# Soprano2G-024.net
KiCad netlist of a schematic drawn in EAGLE
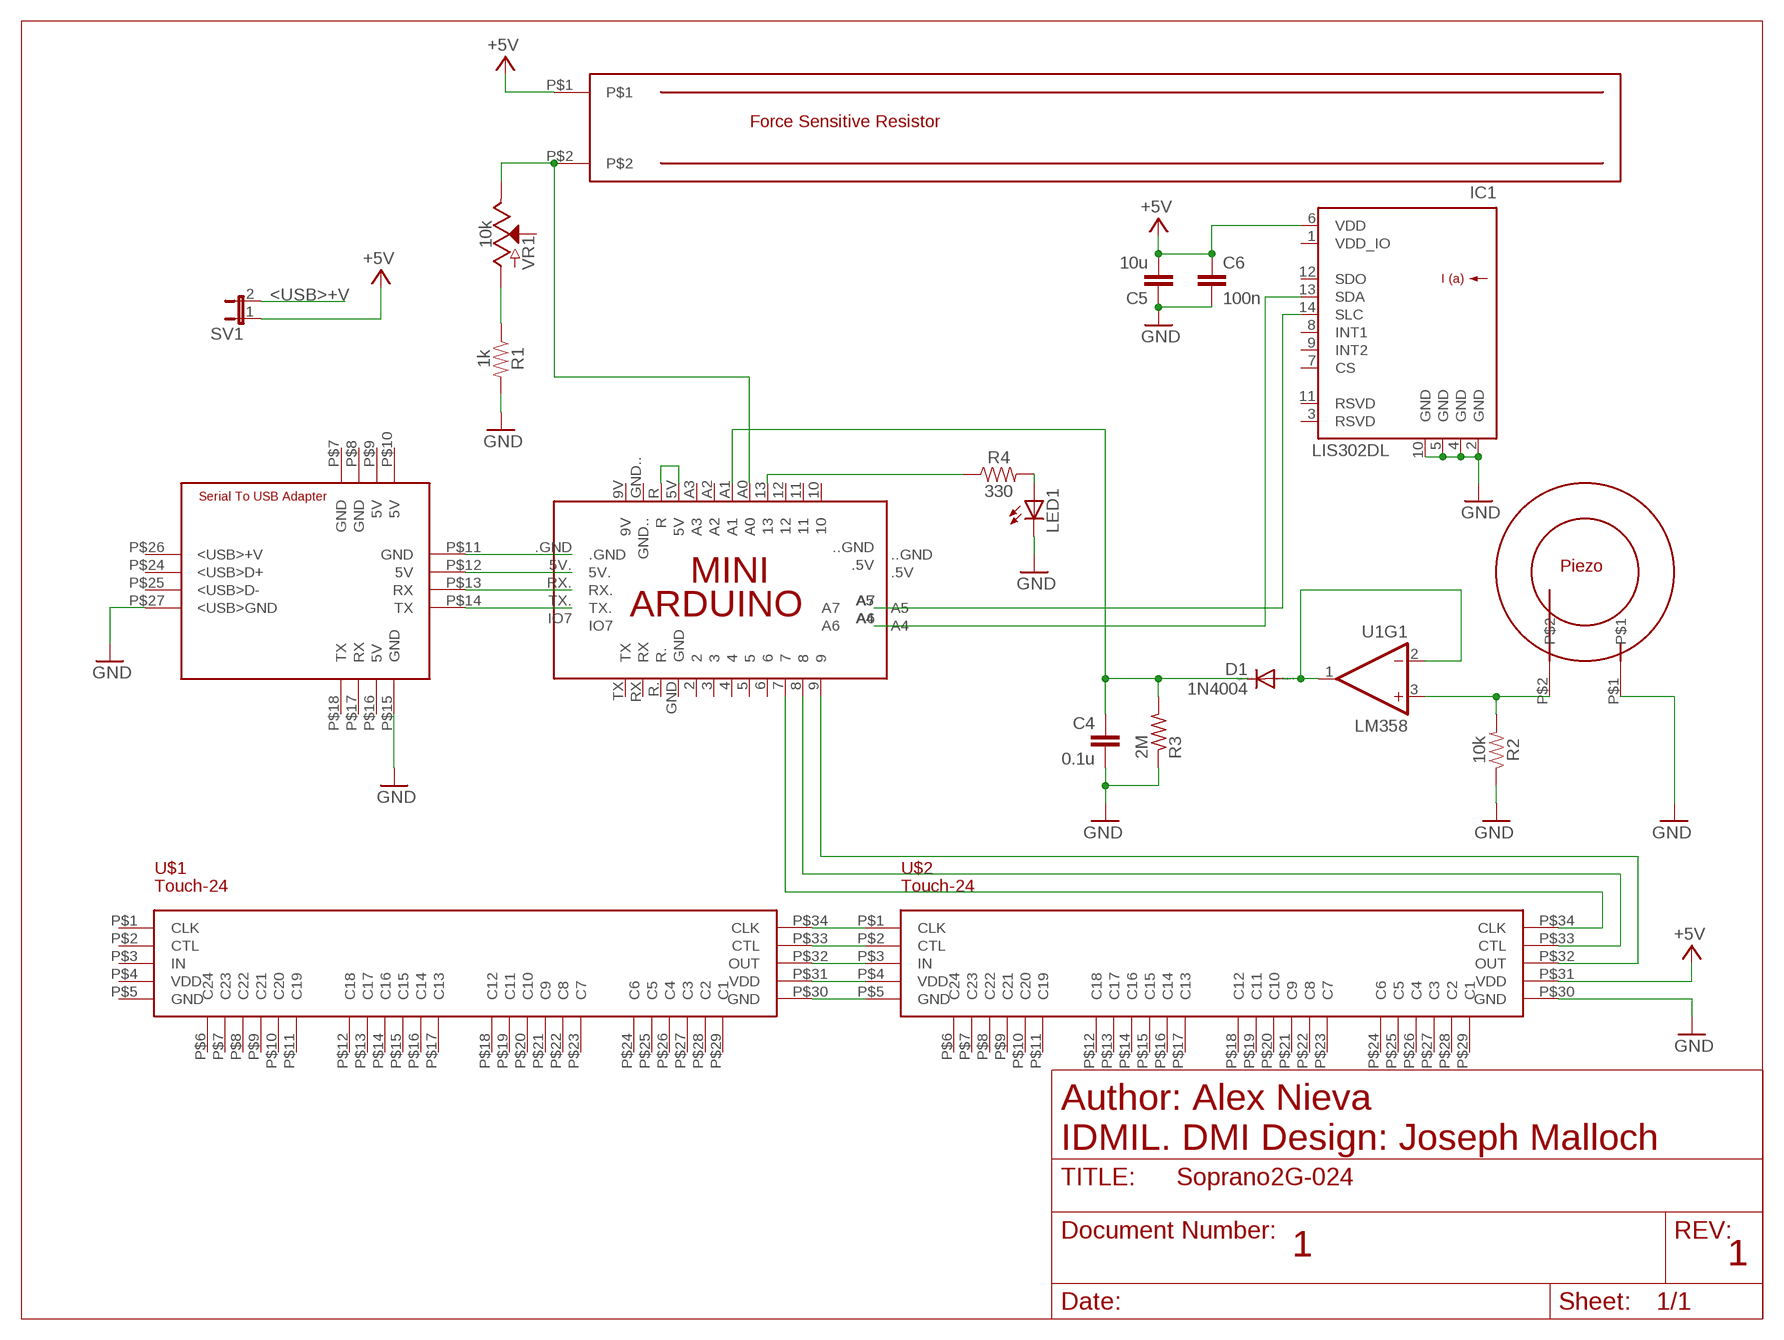
[diagram p0: schematic, sheet 1]

(export (version "E")
  (design (tool "Eeschema 10.0.6"))
  (components
    (comp (ref "C4")
      (value "0.1u")
      (footprint "eagle-import:C5B5.5")
      (libsource (lib "eagle-import") (part "C5/5.5"))
    )
    (comp (ref "C5")
      (value "10u")
      (footprint "eagle-import:C5B5.5")
      (libsource (lib "eagle-import") (part "C5/5.5"))
    )
    (comp (ref "C6")
      (value "100n")
      (footprint "eagle-import:C5B5.5")
      (libsource (lib "eagle-import") (part "C5/5.5"))
    )
    (comp (ref "D1")
      (value "1N4004")
      (footprint "eagle-import:DO41-10")
      (libsource (lib "eagle-import") (part "1N4004"))
    )
    (comp (ref "IC1")
      (value "LIS302DL")
      (footprint "eagle-import:LGA-14")
      (libsource (lib "eagle-import") (part "LIS302DL"))
    )
    (comp (ref "LED1")
      (value "LED3MM")
      (footprint "eagle-import:LED3MM")
      (libsource (lib "eagle-import") (part "LED3MM"))
    )
    (comp (ref "PCB1")
      (value "ARDUINO_MINI")
      (footprint "eagle-import:ARDUINO_MINI")
      (libsource (lib "eagle-import") (part "ARDUINO_MINI"))
    )
    (comp (ref "R1")
      (value "1k")
      (footprint "eagle-import:AXIAL-0.3")
      (libsource (lib "eagle-import") (part "1KOHM-HORIZ-1/4W-1%"))
    )
    (comp (ref "R2")
      (value "10k")
      (footprint "eagle-import:AXIAL-0.3")
      (libsource (lib "eagle-import") (part "10KOHM-HORIZ-1/4W-1%"))
    )
    (comp (ref "R3")
      (value "2M")
      (footprint "eagle-import:0204_7")
      (libsource (lib "eagle-import") (part "R-US_0204/7"))
    )
    (comp (ref "R4")
      (value "330")
      (footprint "eagle-import:AXIAL-0.3")
      (libsource (lib "eagle-import") (part "1KOHM-HORIZ-1/4W-1%"))
    )
    (comp (ref "SV1")
      (value "JP1E")
      (footprint "eagle-import:JP1")
      (libsource (lib "eagle-import") (part "JP1E"))
    )
    (comp (ref "U$1")
      (value "TOUCH-24TOUCH-24")
      (footprint "eagle-import:TOUCH24")
      (libsource (lib "eagle-import") (part "TOUCH-24TOUCH-24"))
    )
    (comp (ref "U$2")
      (value "TOUCH-24TOUCH-24")
      (footprint "eagle-import:TOUCH24")
      (libsource (lib "eagle-import") (part "TOUCH-24TOUCH-24"))
    )
    (comp (ref "U$4")
      (value "SERIAL_TO_USB_ARDUINO_MINI")
      (footprint "eagle-import:SERIAL_TO_USB_ARDUINO")
      (libsource (lib "eagle-import") (part "SERIAL_TO_USB_ARDUINO_MINI"))
    )
    (comp (ref "U$5")
      (value "FSR_T-STICK")
      (footprint "eagle-import:FSR_T-STICK")
      (libsource (lib "eagle-import") (part "FSR_T-STICK"))
    )
    (comp (ref "U$6")
      (value "PIEZO_TSTICK")
      (footprint "eagle-import:PIEZO_TSTICK")
      (libsource (lib "eagle-import") (part "PIEZO_TSTICK"))
    )
    (comp (ref "U1")
      (value "LM358")
      (footprint "eagle-import:DIP08")
      (libsource (lib "eagle-import") (part "LM358"))
    )
    (comp (ref "VR1")
      (value "10k")
      (footprint "eagle-import:POT-PTH-ALPS")
      (libsource (lib "eagle-import") (part "POTENTIOMETER-PTH-9MM-1/20W-20%"))
    )
  )
  (nets
    (net (code "1") (name "+5V") (class "Default")
      (node (ref "C5") (pin "2") (pinfunction "2_2") (pintype "passive"))
      (node (ref "C6") (pin "1") (pinfunction "1_1") (pintype "passive"))
      (node (ref "IC1") (pin "6") (pinfunction "VDD_6") (pintype "power_in"))
      (node (ref "PCB1") (pin "5V.") (pinfunction "5V._5V.") (pintype "bidirectional"))
      (node (ref "SV1") (pin "1") (pinfunction "1_1") (pintype "passive"))
      (node (ref "U$2") (pin "P$31") (pinfunction "VDD_P$31") (pintype "bidirectional"))
      (node (ref "U$4") (pin "P$12") (pinfunction "5V_P$12") (pintype "bidirectional"))
      (node (ref "U$5") (pin "P$1") (pinfunction "P$1_P$1") (pintype "bidirectional"))
    )
    (net (code "2") (name "/<USB>+V") (class "Default")
      (node (ref "SV1") (pin "2") (pinfunction "2_2") (pintype "passive"))
    )
    (net (code "3") (name "/VDD_IO") (class "Default")
      (node (ref "IC1") (pin "1") (pinfunction "VDD_IO_1") (pintype "power_in"))
    )
    (net (code "4") (name "GND") (class "Default")
      (node (ref "C4") (pin "2") (pinfunction "2_2") (pintype "passive"))
      (node (ref "C5") (pin "1") (pinfunction "1_1") (pintype "passive"))
      (node (ref "C6") (pin "2") (pinfunction "2_2") (pintype "passive"))
      (node (ref "IC1") (pin "10") (pinfunction "GND_10") (pintype "passive"))
      (node (ref "IC1") (pin "2") (pinfunction "GND_2") (pintype "power_in"))
      (node (ref "IC1") (pin "4") (pinfunction "GND_4") (pintype "passive"))
      (node (ref "IC1") (pin "5") (pinfunction "GND_5") (pintype "passive"))
      (node (ref "LED1") (pin "K") (pinfunction "C_K") (pintype "passive"))
      (node (ref "R1") (pin "P$2") (pinfunction "2_P$2") (pintype "passive"))
      (node (ref "R2") (pin "P$1") (pinfunction "1_P$1") (pintype "passive"))
      (node (ref "R3") (pin "1") (pinfunction "1_1") (pintype "passive"))
      (node (ref "U$2") (pin "P$30") (pinfunction "GND_P$30") (pintype "bidirectional"))
      (node (ref "U$4") (pin "P$15") (pinfunction "GND_P$15") (pintype "bidirectional"))
      (node (ref "U$4") (pin "P$27") (pinfunction "<USB>GND_P$27") (pintype "bidirectional"))
      (node (ref "U$6") (pin "P$1") (pinfunction "P$1_P$1") (pintype "bidirectional"))
    )
    (net (code "5") (name "Net-(C4-Pad1)") (class "Default")
      (node (ref "C4") (pin "1") (pinfunction "1_1") (pintype "passive"))
      (node (ref "D1") (pin "C") (pinfunction "C_C") (pintype "passive"))
      (node (ref "PCB1") (pin "A1") (pinfunction "A1_A1") (pintype "bidirectional"))
      (node (ref "R3") (pin "2") (pinfunction "2_2") (pintype "passive"))
    )
    (net (code "6") (name "Net-(IC1-SDA)") (class "Default")
      (node (ref "IC1") (pin "13") (pinfunction "SDA_13") (pintype "bidirectional"))
      (node (ref "PCB1") (pin "A4") (pinfunction "A4_A4") (pintype "bidirectional"))
    )
    (net (code "7") (name "Net-(IC1-SLC)") (class "Default")
      (node (ref "IC1") (pin "14") (pinfunction "SLC_14") (pintype "bidirectional"))
      (node (ref "PCB1") (pin "A5") (pinfunction "A5_A5") (pintype "bidirectional"))
    )
    (net (code "8") (name "Net-(PCB1-Pad.GND)") (class "Default")
      (node (ref "PCB1") (pin ".GND") (pinfunction ".GND_.GND") (pintype "bidirectional"))
      (node (ref "U$4") (pin "P$11") (pinfunction "GND_P$11") (pintype "bidirectional"))
    )
    (net (code "9") (name "Net-(PCB1-Pad5V)") (class "Default")
      (node (ref "PCB1") (pin "5V") (pinfunction "5V_5V") (pintype "bidirectional"))
      (node (ref "PCB1") (pin "R") (pinfunction "R_R") (pintype "bidirectional"))
    )
    (net (code "10") (name "Net-(PCB1-Pad7)") (class "Default")
      (node (ref "PCB1") (pin "7") (pinfunction "7_7") (pintype "bidirectional"))
      (node (ref "U$2") (pin "P$34") (pinfunction "CLK_P$34") (pintype "bidirectional"))
    )
    (net (code "11") (name "Net-(PCB1-Pad8)") (class "Default")
      (node (ref "PCB1") (pin "8") (pinfunction "8_8") (pintype "bidirectional"))
      (node (ref "U$2") (pin "P$33") (pinfunction "CTL_P$33") (pintype "bidirectional"))
    )
    (net (code "12") (name "Net-(PCB1-PadRX.)") (class "Default")
      (node (ref "PCB1") (pin "RX.") (pinfunction "RX._RX.") (pintype "bidirectional"))
      (node (ref "U$4") (pin "P$13") (pinfunction "RX_P$13") (pintype "bidirectional"))
    )
    (net (code "13") (name "Net-(PCB1-PadTX.)") (class "Default")
      (node (ref "PCB1") (pin "TX.") (pinfunction "TX._TX.") (pintype "bidirectional"))
      (node (ref "U$4") (pin "P$14") (pinfunction "TX_P$14") (pintype "bidirectional"))
    )
    (net (code "14") (name "Net-(R1-1)") (class "Default")
      (node (ref "R1") (pin "P$1") (pinfunction "1_P$1") (pintype "passive"))
      (node (ref "VR1") (pin "P$3") (pinfunction "A_P$3") (pintype "passive"))
    )
    (net (code "15") (name "Net-(R2-2)") (class "Default")
      (node (ref "R2") (pin "P$2") (pinfunction "2_P$2") (pintype "passive"))
      (node (ref "U$6") (pin "P$2") (pinfunction "P$2_P$2") (pintype "bidirectional"))
      (node (ref "U1") (pin "3") (pinfunction "+IN_3") (pintype "input"))
    )
    (net (code "16") (name "Net-(R4-1)") (class "Default")
      (node (ref "PCB1") (pin "13") (pinfunction "13_13") (pintype "bidirectional"))
      (node (ref "R4") (pin "P$1") (pinfunction "1_P$1") (pintype "passive"))
    )
    (net (code "17") (name "Net-(R4-2)") (class "Default")
      (node (ref "LED1") (pin "A") (pinfunction "A_A") (pintype "passive"))
      (node (ref "R4") (pin "P$2") (pinfunction "2_P$2") (pintype "passive"))
    )
    (net (code "18") (name "Net-(U$1-CLK-PadP$34)") (class "Default")
      (node (ref "U$1") (pin "P$34") (pinfunction "CLK_P$34") (pintype "bidirectional"))
      (node (ref "U$2") (pin "P$1") (pinfunction "CLK_P$1") (pintype "bidirectional"))
    )
    (net (code "19") (name "Net-(U$1-CTL-PadP$33)") (class "Default")
      (node (ref "U$1") (pin "P$33") (pinfunction "CTL_P$33") (pintype "bidirectional"))
      (node (ref "U$2") (pin "P$2") (pinfunction "CTL_P$2") (pintype "bidirectional"))
    )
    (net (code "20") (name "Net-(U$1-GND-PadP$30)") (class "Default")
      (node (ref "U$1") (pin "P$30") (pinfunction "GND_P$30") (pintype "bidirectional"))
      (node (ref "U$2") (pin "P$5") (pinfunction "GND_P$5") (pintype "bidirectional"))
    )
    (net (code "21") (name "Net-(U$1-OUT)") (class "Default")
      (node (ref "U$1") (pin "P$32") (pinfunction "OUT_P$32") (pintype "bidirectional"))
      (node (ref "U$2") (pin "P$3") (pinfunction "IN_P$3") (pintype "bidirectional"))
    )
    (net (code "22") (name "Net-(U$1-VDD-PadP$31)") (class "Default")
      (node (ref "U$1") (pin "P$31") (pinfunction "VDD_P$31") (pintype "bidirectional"))
      (node (ref "U$2") (pin "P$4") (pinfunction "VDD_P$4") (pintype "bidirectional"))
    )
    (net (code "23") (name "Net-(U$2-OUT)") (class "Default")
      (node (ref "PCB1") (pin "9") (pinfunction "9_9") (pintype "bidirectional"))
      (node (ref "U$2") (pin "P$32") (pinfunction "OUT_P$32") (pintype "bidirectional"))
    )
    (net (code "24") (name "Net-(U1A--IN)") (class "Default")
      (node (ref "D1") (pin "A") (pinfunction "A_A") (pintype "passive"))
      (node (ref "U1") (pin "1") (pinfunction "OUT_1") (pintype "output"))
      (node (ref "U1") (pin "2") (pinfunction "-IN_2") (pintype "input"))
    )
    (net (code "25") (name "Net-(VR1-E)") (class "Default")
      (node (ref "PCB1") (pin "A0") (pinfunction "A0_A0") (pintype "bidirectional"))
      (node (ref "U$5") (pin "P$2") (pinfunction "P$2_P$2") (pintype "bidirectional"))
      (node (ref "VR1") (pin "P$1") (pinfunction "E_P$1") (pintype "passive"))
    )
    (net (code "26") (name "unconnected-(IC1-CS-Pad7)") (class "Default")
      (node (ref "IC1") (pin "7") (pinfunction "CS_7") (pintype "bidirectional"))
    )
    (net (code "27") (name "unconnected-(IC1-INT1-Pad8)") (class "Default")
      (node (ref "IC1") (pin "8") (pinfunction "INT1_8") (pintype "bidirectional"))
    )
    (net (code "28") (name "unconnected-(IC1-INT2-Pad9)") (class "Default")
      (node (ref "IC1") (pin "9") (pinfunction "INT2_9") (pintype "bidirectional"))
    )
    (net (code "29") (name "unconnected-(IC1-RSVD-Pad3)") (class "Default")
      (node (ref "IC1") (pin "3") (pinfunction "RSVD_3") (pintype "passive"))
    )
    (net (code "30") (name "unconnected-(IC1-RSVD-Pad11)") (class "Default")
      (node (ref "IC1") (pin "11") (pinfunction "RSVD_11") (pintype "passive"))
    )
    (net (code "31") (name "unconnected-(IC1-SDO-Pad12)") (class "Default")
      (node (ref "IC1") (pin "12") (pinfunction "SDO_12") (pintype "bidirectional"))
    )
    (net (code "32") (name "unconnected-(PCB1-Pad..GND)") (class "Default")
      (node (ref "PCB1") (pin "..GND") (pinfunction "..GND_..GND") (pintype "bidirectional"))
    )
    (net (code "33") (name "unconnected-(PCB1-Pad.5V)") (class "Default")
      (node (ref "PCB1") (pin ".5V") (pinfunction ".5V_.5V") (pintype "bidirectional"))
    )
    (net (code "34") (name "unconnected-(PCB1-Pad2)") (class "Default")
      (node (ref "PCB1") (pin "2") (pinfunction "2_2") (pintype "bidirectional"))
    )
    (net (code "35") (name "unconnected-(PCB1-Pad3)") (class "Default")
      (node (ref "PCB1") (pin "3") (pinfunction "3_3") (pintype "bidirectional"))
    )
    (net (code "36") (name "unconnected-(PCB1-Pad4)") (class "Default")
      (node (ref "PCB1") (pin "4") (pinfunction "4_4") (pintype "bidirectional"))
    )
    (net (code "37") (name "unconnected-(PCB1-Pad5)") (class "Default")
      (node (ref "PCB1") (pin "5") (pinfunction "5_5") (pintype "bidirectional"))
    )
    (net (code "38") (name "unconnected-(PCB1-Pad6)") (class "Default")
      (node (ref "PCB1") (pin "6") (pinfunction "6_6") (pintype "bidirectional"))
    )
    (net (code "39") (name "unconnected-(PCB1-Pad9V)") (class "Default")
      (node (ref "PCB1") (pin "9V") (pinfunction "9V_9V") (pintype "bidirectional"))
    )
    (net (code "40") (name "unconnected-(PCB1-Pad10)") (class "Default")
      (node (ref "PCB1") (pin "10") (pinfunction "10_10") (pintype "bidirectional"))
    )
    (net (code "41") (name "unconnected-(PCB1-Pad11)") (class "Default")
      (node (ref "PCB1") (pin "11") (pinfunction "11_11") (pintype "bidirectional"))
    )
    (net (code "42") (name "unconnected-(PCB1-Pad12)") (class "Default")
      (node (ref "PCB1") (pin "12") (pinfunction "12_12") (pintype "bidirectional"))
    )
    (net (code "43") (name "unconnected-(PCB1-PadA2)") (class "Default")
      (node (ref "PCB1") (pin "A2") (pinfunction "A2_A2") (pintype "bidirectional"))
    )
    (net (code "44") (name "unconnected-(PCB1-PadA3)") (class "Default")
      (node (ref "PCB1") (pin "A3") (pinfunction "A3_A3") (pintype "bidirectional"))
    )
    (net (code "45") (name "unconnected-(PCB1-PadA6)") (class "Default")
      (node (ref "PCB1") (pin "A6") (pinfunction "A6_A6") (pintype "bidirectional"))
    )
    (net (code "46") (name "unconnected-(PCB1-PadA7)") (class "Default")
      (node (ref "PCB1") (pin "A7") (pinfunction "A7_A7") (pintype "bidirectional"))
    )
    (net (code "47") (name "unconnected-(PCB1-PadGND)") (class "Default")
      (node (ref "PCB1") (pin "GND") (pinfunction "GND_GND") (pintype "bidirectional"))
    )
    (net (code "48") (name "unconnected-(PCB1-PadGND..)") (class "Default")
      (node (ref "PCB1") (pin "GND..") (pinfunction "GND.._GND..") (pintype "bidirectional"))
    )
    (net (code "49") (name "unconnected-(PCB1-PadIO7)") (class "Default")
      (node (ref "PCB1") (pin "IO7") (pinfunction "IO7_IO7") (pintype "bidirectional"))
    )
    (net (code "50") (name "unconnected-(PCB1-PadR.)") (class "Default")
      (node (ref "PCB1") (pin "R.") (pinfunction "R._R.") (pintype "bidirectional"))
    )
    (net (code "51") (name "unconnected-(PCB1-PadRX)") (class "Default")
      (node (ref "PCB1") (pin "RX") (pinfunction "RX_RX") (pintype "bidirectional"))
    )
    (net (code "52") (name "unconnected-(PCB1-PadTX)") (class "Default")
      (node (ref "PCB1") (pin "TX") (pinfunction "TX_TX") (pintype "bidirectional"))
    )
    (net (code "53") (name "unconnected-(U$1-C1-PadP$29)") (class "Default")
      (node (ref "U$1") (pin "P$29") (pinfunction "C1_P$29") (pintype "bidirectional"))
    )
    (net (code "54") (name "unconnected-(U$1-C2-PadP$28)") (class "Default")
      (node (ref "U$1") (pin "P$28") (pinfunction "C2_P$28") (pintype "bidirectional"))
    )
    (net (code "55") (name "unconnected-(U$1-C3-PadP$27)") (class "Default")
      (node (ref "U$1") (pin "P$27") (pinfunction "C3_P$27") (pintype "bidirectional"))
    )
    (net (code "56") (name "unconnected-(U$1-C4-PadP$26)") (class "Default")
      (node (ref "U$1") (pin "P$26") (pinfunction "C4_P$26") (pintype "bidirectional"))
    )
    (net (code "57") (name "unconnected-(U$1-C5-PadP$25)") (class "Default")
      (node (ref "U$1") (pin "P$25") (pinfunction "C5_P$25") (pintype "bidirectional"))
    )
    (net (code "58") (name "unconnected-(U$1-C6-PadP$24)") (class "Default")
      (node (ref "U$1") (pin "P$24") (pinfunction "C6_P$24") (pintype "bidirectional"))
    )
    (net (code "59") (name "unconnected-(U$1-C7-PadP$23)") (class "Default")
      (node (ref "U$1") (pin "P$23") (pinfunction "C7_P$23") (pintype "bidirectional"))
    )
    (net (code "60") (name "unconnected-(U$1-C8-PadP$22)") (class "Default")
      (node (ref "U$1") (pin "P$22") (pinfunction "C8_P$22") (pintype "bidirectional"))
    )
    (net (code "61") (name "unconnected-(U$1-C9-PadP$21)") (class "Default")
      (node (ref "U$1") (pin "P$21") (pinfunction "C9_P$21") (pintype "bidirectional"))
    )
    (net (code "62") (name "unconnected-(U$1-C10-PadP$20)") (class "Default")
      (node (ref "U$1") (pin "P$20") (pinfunction "C10_P$20") (pintype "bidirectional"))
    )
    (net (code "63") (name "unconnected-(U$1-C11-PadP$19)") (class "Default")
      (node (ref "U$1") (pin "P$19") (pinfunction "C11_P$19") (pintype "bidirectional"))
    )
    (net (code "64") (name "unconnected-(U$1-C12-PadP$18)") (class "Default")
      (node (ref "U$1") (pin "P$18") (pinfunction "C12_P$18") (pintype "bidirectional"))
    )
    (net (code "65") (name "unconnected-(U$1-C13-PadP$17)") (class "Default")
      (node (ref "U$1") (pin "P$17") (pinfunction "C13_P$17") (pintype "bidirectional"))
    )
    (net (code "66") (name "unconnected-(U$1-C14-PadP$16)") (class "Default")
      (node (ref "U$1") (pin "P$16") (pinfunction "C14_P$16") (pintype "bidirectional"))
    )
    (net (code "67") (name "unconnected-(U$1-C15-PadP$15)") (class "Default")
      (node (ref "U$1") (pin "P$15") (pinfunction "C15_P$15") (pintype "bidirectional"))
    )
    (net (code "68") (name "unconnected-(U$1-C16-PadP$14)") (class "Default")
      (node (ref "U$1") (pin "P$14") (pinfunction "C16_P$14") (pintype "bidirectional"))
    )
    (net (code "69") (name "unconnected-(U$1-C17-PadP$13)") (class "Default")
      (node (ref "U$1") (pin "P$13") (pinfunction "C17_P$13") (pintype "bidirectional"))
    )
    (net (code "70") (name "unconnected-(U$1-C18-PadP$12)") (class "Default")
      (node (ref "U$1") (pin "P$12") (pinfunction "C18_P$12") (pintype "bidirectional"))
    )
    (net (code "71") (name "unconnected-(U$1-C19-PadP$11)") (class "Default")
      (node (ref "U$1") (pin "P$11") (pinfunction "C19_P$11") (pintype "bidirectional"))
    )
    (net (code "72") (name "unconnected-(U$1-C20-PadP$10)") (class "Default")
      (node (ref "U$1") (pin "P$10") (pinfunction "C20_P$10") (pintype "bidirectional"))
    )
    (net (code "73") (name "unconnected-(U$1-C21-PadP$9)") (class "Default")
      (node (ref "U$1") (pin "P$9") (pinfunction "C21_P$9") (pintype "bidirectional"))
    )
    (net (code "74") (name "unconnected-(U$1-C22-PadP$8)") (class "Default")
      (node (ref "U$1") (pin "P$8") (pinfunction "C22_P$8") (pintype "bidirectional"))
    )
    (net (code "75") (name "unconnected-(U$1-C23-PadP$7)") (class "Default")
      (node (ref "U$1") (pin "P$7") (pinfunction "C23_P$7") (pintype "bidirectional"))
    )
    (net (code "76") (name "unconnected-(U$1-C24-PadP$6)") (class "Default")
      (node (ref "U$1") (pin "P$6") (pinfunction "C24_P$6") (pintype "bidirectional"))
    )
    (net (code "77") (name "unconnected-(U$1-CLK-PadP$1)") (class "Default")
      (node (ref "U$1") (pin "P$1") (pinfunction "CLK_P$1") (pintype "bidirectional"))
    )
    (net (code "78") (name "unconnected-(U$1-CTL-PadP$2)") (class "Default")
      (node (ref "U$1") (pin "P$2") (pinfunction "CTL_P$2") (pintype "bidirectional"))
    )
    (net (code "79") (name "unconnected-(U$1-GND-PadP$5)") (class "Default")
      (node (ref "U$1") (pin "P$5") (pinfunction "GND_P$5") (pintype "bidirectional"))
    )
    (net (code "80") (name "unconnected-(U$1-IN-PadP$3)") (class "Default")
      (node (ref "U$1") (pin "P$3") (pinfunction "IN_P$3") (pintype "bidirectional"))
    )
    (net (code "81") (name "unconnected-(U$1-VDD-PadP$4)") (class "Default")
      (node (ref "U$1") (pin "P$4") (pinfunction "VDD_P$4") (pintype "bidirectional"))
    )
    (net (code "82") (name "unconnected-(U$2-C1-PadP$29)") (class "Default")
      (node (ref "U$2") (pin "P$29") (pinfunction "C1_P$29") (pintype "bidirectional"))
    )
    (net (code "83") (name "unconnected-(U$2-C2-PadP$28)") (class "Default")
      (node (ref "U$2") (pin "P$28") (pinfunction "C2_P$28") (pintype "bidirectional"))
    )
    (net (code "84") (name "unconnected-(U$2-C3-PadP$27)") (class "Default")
      (node (ref "U$2") (pin "P$27") (pinfunction "C3_P$27") (pintype "bidirectional"))
    )
    (net (code "85") (name "unconnected-(U$2-C4-PadP$26)") (class "Default")
      (node (ref "U$2") (pin "P$26") (pinfunction "C4_P$26") (pintype "bidirectional"))
    )
    (net (code "86") (name "unconnected-(U$2-C5-PadP$25)") (class "Default")
      (node (ref "U$2") (pin "P$25") (pinfunction "C5_P$25") (pintype "bidirectional"))
    )
    (net (code "87") (name "unconnected-(U$2-C6-PadP$24)") (class "Default")
      (node (ref "U$2") (pin "P$24") (pinfunction "C6_P$24") (pintype "bidirectional"))
    )
    (net (code "88") (name "unconnected-(U$2-C7-PadP$23)") (class "Default")
      (node (ref "U$2") (pin "P$23") (pinfunction "C7_P$23") (pintype "bidirectional"))
    )
    (net (code "89") (name "unconnected-(U$2-C8-PadP$22)") (class "Default")
      (node (ref "U$2") (pin "P$22") (pinfunction "C8_P$22") (pintype "bidirectional"))
    )
    (net (code "90") (name "unconnected-(U$2-C9-PadP$21)") (class "Default")
      (node (ref "U$2") (pin "P$21") (pinfunction "C9_P$21") (pintype "bidirectional"))
    )
    (net (code "91") (name "unconnected-(U$2-C10-PadP$20)") (class "Default")
      (node (ref "U$2") (pin "P$20") (pinfunction "C10_P$20") (pintype "bidirectional"))
    )
    (net (code "92") (name "unconnected-(U$2-C11-PadP$19)") (class "Default")
      (node (ref "U$2") (pin "P$19") (pinfunction "C11_P$19") (pintype "bidirectional"))
    )
    (net (code "93") (name "unconnected-(U$2-C12-PadP$18)") (class "Default")
      (node (ref "U$2") (pin "P$18") (pinfunction "C12_P$18") (pintype "bidirectional"))
    )
    (net (code "94") (name "unconnected-(U$2-C13-PadP$17)") (class "Default")
      (node (ref "U$2") (pin "P$17") (pinfunction "C13_P$17") (pintype "bidirectional"))
    )
    (net (code "95") (name "unconnected-(U$2-C14-PadP$16)") (class "Default")
      (node (ref "U$2") (pin "P$16") (pinfunction "C14_P$16") (pintype "bidirectional"))
    )
    (net (code "96") (name "unconnected-(U$2-C15-PadP$15)") (class "Default")
      (node (ref "U$2") (pin "P$15") (pinfunction "C15_P$15") (pintype "bidirectional"))
    )
    (net (code "97") (name "unconnected-(U$2-C16-PadP$14)") (class "Default")
      (node (ref "U$2") (pin "P$14") (pinfunction "C16_P$14") (pintype "bidirectional"))
    )
    (net (code "98") (name "unconnected-(U$2-C17-PadP$13)") (class "Default")
      (node (ref "U$2") (pin "P$13") (pinfunction "C17_P$13") (pintype "bidirectional"))
    )
    (net (code "99") (name "unconnected-(U$2-C18-PadP$12)") (class "Default")
      (node (ref "U$2") (pin "P$12") (pinfunction "C18_P$12") (pintype "bidirectional"))
    )
    (net (code "100") (name "unconnected-(U$2-C19-PadP$11)") (class "Default")
      (node (ref "U$2") (pin "P$11") (pinfunction "C19_P$11") (pintype "bidirectional"))
    )
    (net (code "101") (name "unconnected-(U$2-C20-PadP$10)") (class "Default")
      (node (ref "U$2") (pin "P$10") (pinfunction "C20_P$10") (pintype "bidirectional"))
    )
    (net (code "102") (name "unconnected-(U$2-C21-PadP$9)") (class "Default")
      (node (ref "U$2") (pin "P$9") (pinfunction "C21_P$9") (pintype "bidirectional"))
    )
    (net (code "103") (name "unconnected-(U$2-C22-PadP$8)") (class "Default")
      (node (ref "U$2") (pin "P$8") (pinfunction "C22_P$8") (pintype "bidirectional"))
    )
    (net (code "104") (name "unconnected-(U$2-C23-PadP$7)") (class "Default")
      (node (ref "U$2") (pin "P$7") (pinfunction "C23_P$7") (pintype "bidirectional"))
    )
    (net (code "105") (name "unconnected-(U$2-C24-PadP$6)") (class "Default")
      (node (ref "U$2") (pin "P$6") (pinfunction "C24_P$6") (pintype "bidirectional"))
    )
    (net (code "106") (name "unconnected-(U$4-5V-PadP$9)") (class "Default")
      (node (ref "U$4") (pin "P$9") (pinfunction "5V_P$9") (pintype "bidirectional"))
    )
    (net (code "107") (name "unconnected-(U$4-5V-PadP$10)") (class "Default")
      (node (ref "U$4") (pin "P$10") (pinfunction "5V_P$10") (pintype "bidirectional"))
    )
    (net (code "108") (name "unconnected-(U$4-5V-PadP$16)") (class "Default")
      (node (ref "U$4") (pin "P$16") (pinfunction "5V_P$16") (pintype "bidirectional"))
    )
    (net (code "109") (name "unconnected-(U$4-<USB>+V-PadP$26)") (class "Default")
      (node (ref "U$4") (pin "P$26") (pinfunction "<USB>+V_P$26") (pintype "bidirectional"))
    )
    (net (code "110") (name "unconnected-(U$4-<USB>D+-PadP$24)") (class "Default")
      (node (ref "U$4") (pin "P$24") (pinfunction "<USB>D+_P$24") (pintype "bidirectional"))
    )
    (net (code "111") (name "unconnected-(U$4-<USB>D--PadP$25)") (class "Default")
      (node (ref "U$4") (pin "P$25") (pinfunction "<USB>D-_P$25") (pintype "bidirectional"))
    )
    (net (code "112") (name "unconnected-(U$4-GND-PadP$7)") (class "Default")
      (node (ref "U$4") (pin "P$7") (pinfunction "GND_P$7") (pintype "bidirectional"))
    )
    (net (code "113") (name "unconnected-(U$4-GND-PadP$8)") (class "Default")
      (node (ref "U$4") (pin "P$8") (pinfunction "GND_P$8") (pintype "bidirectional"))
    )
    (net (code "114") (name "unconnected-(U$4-RX-PadP$17)") (class "Default")
      (node (ref "U$4") (pin "P$17") (pinfunction "RX_P$17") (pintype "bidirectional"))
    )
    (net (code "115") (name "unconnected-(U$4-TX-PadP$18)") (class "Default")
      (node (ref "U$4") (pin "P$18") (pinfunction "TX_P$18") (pintype "bidirectional"))
    )
    (net (code "116") (name "unconnected-(VR1-S-PadP$2)") (class "Default")
      (node (ref "VR1") (pin "P$2") (pinfunction "S_P$2") (pintype "passive"))
    )
  )
)
